# CurrentSensors.net
KiCad netlist of a schematic drawn in Altium Designer
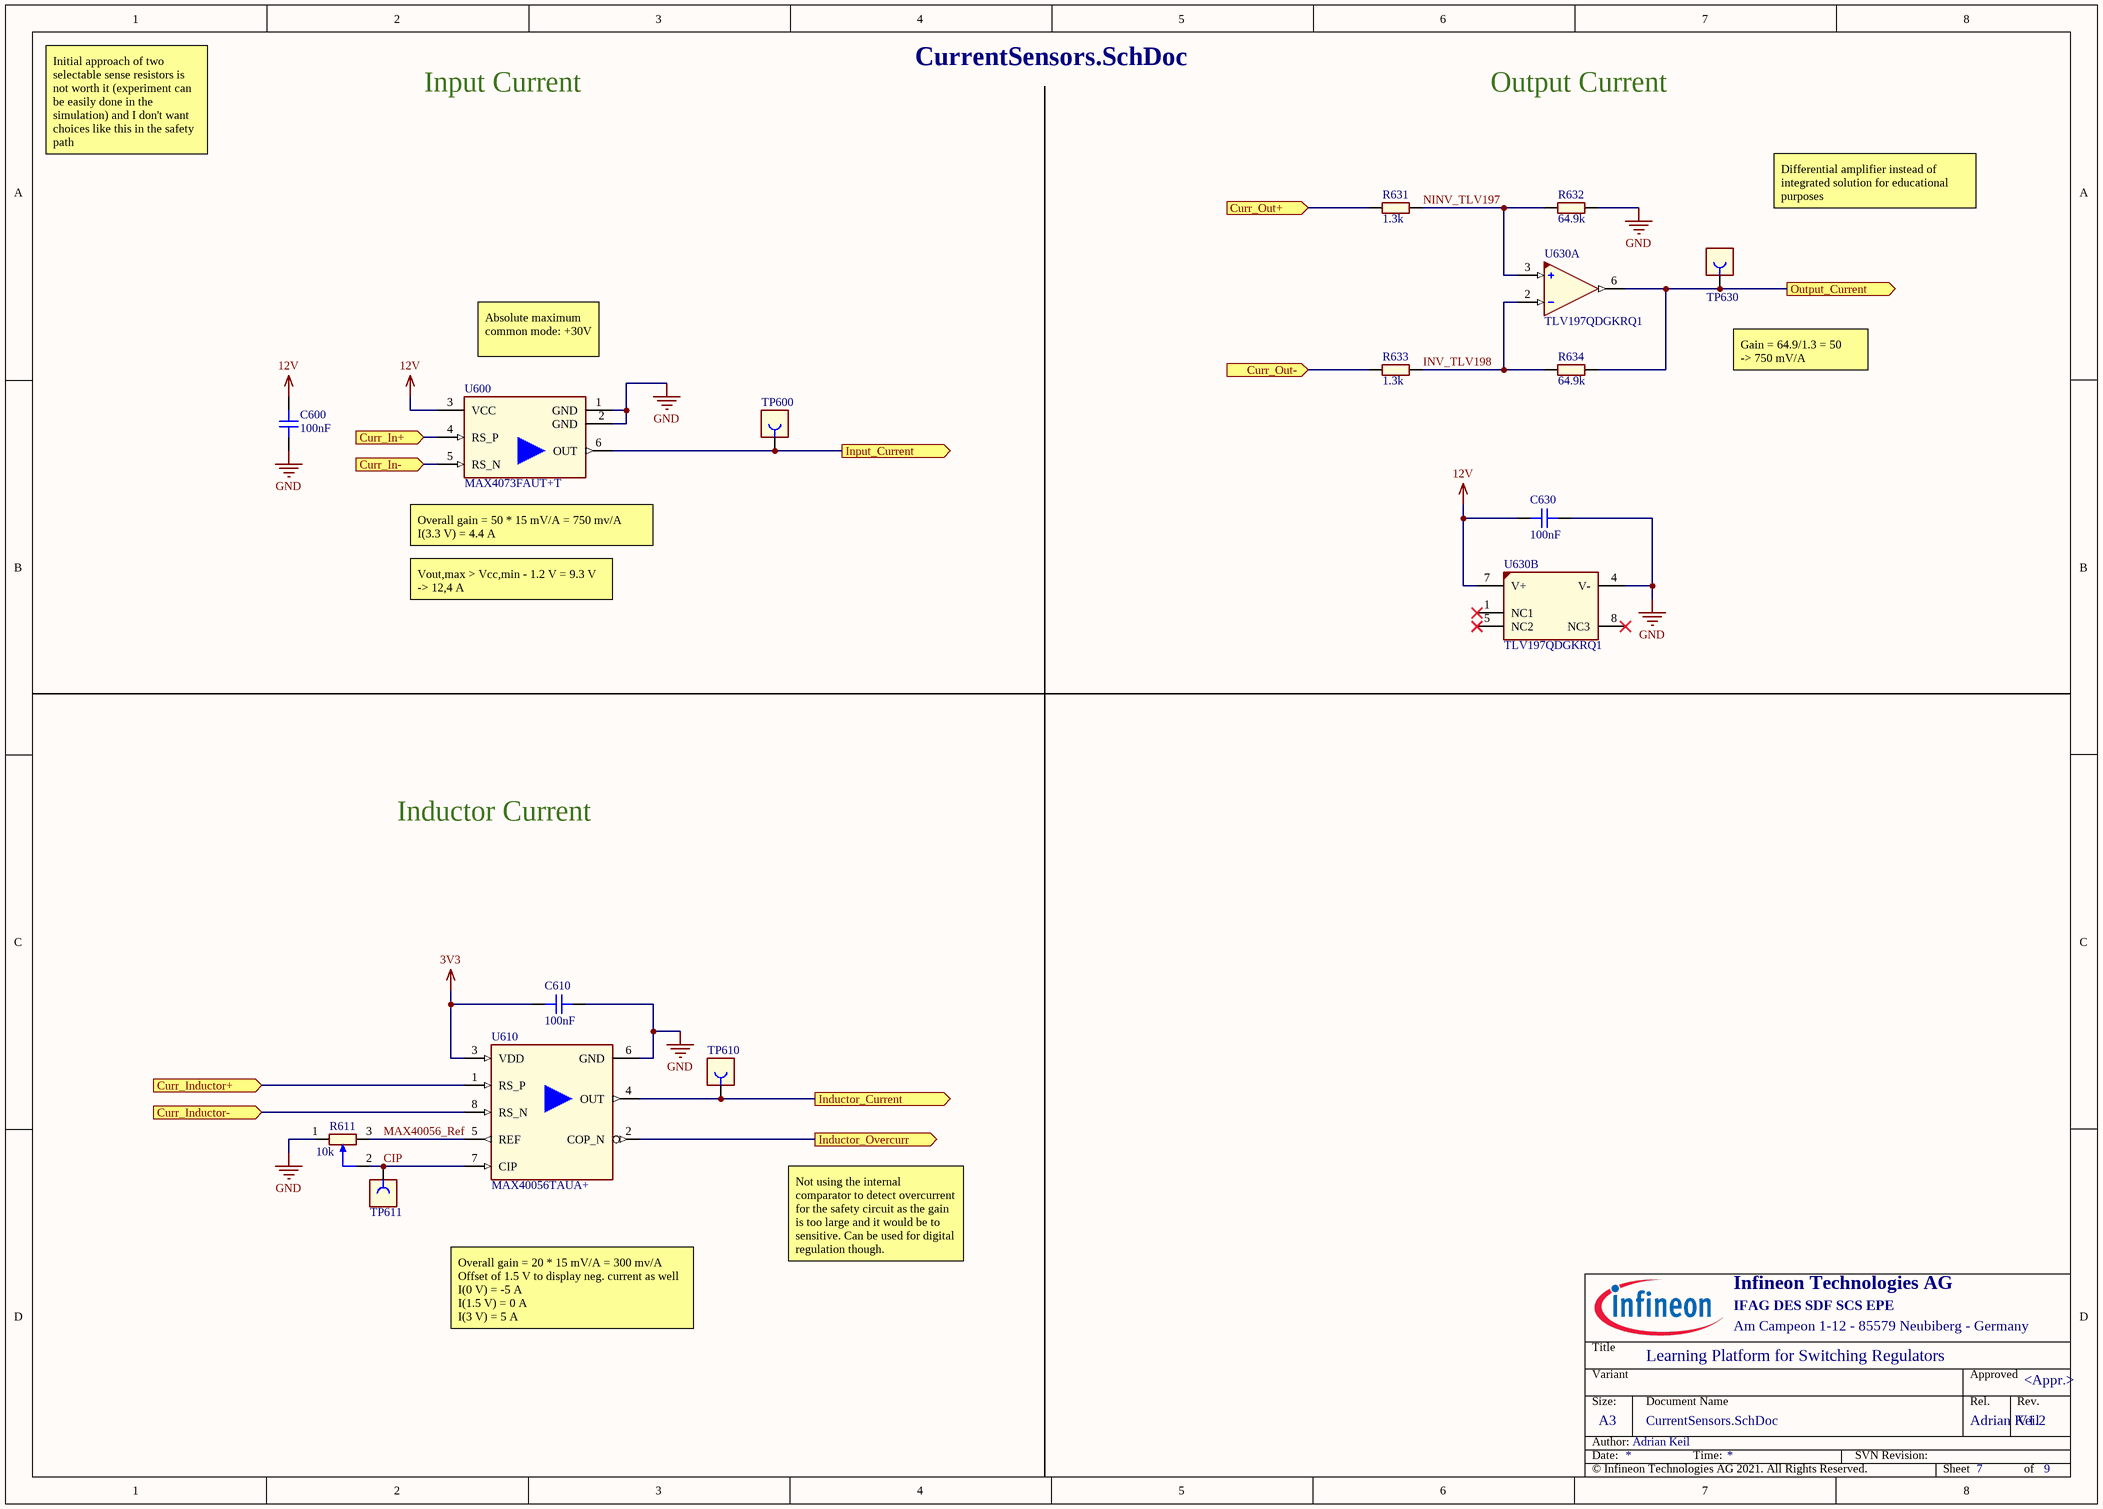
[diagram p0: CurrentSensors.SchDoc]

(export (version "E")
  (design (tool "Eeschema 10.0.6"))
  (components
    (comp (ref "C600")
      (value "100nF")
      (footprint "CAPC1608X90N-2")
      (description "CAP / CERA / 100nF / 50V / 10% / X7R (EIA) / -55°C to 125°C / 0603 / SMD / -")
      (fields (field (name "MANUFACTURER") "AVX"))
      (libsource (lib "PCBLibraryData") (part "CAP-SGL-STD-02P_00000001"))
    )
    (comp (ref "C610")
      (value "100nF")
      (footprint "CAPC1608X90N-2")
      (description "CAP / CERA / 100nF / 50V / 10% / X7R (EIA) / -55°C to 125°C / 0603 / SMD / -")
      (fields (field (name "MANUFACTURER") "AVX"))
      (libsource (lib "PCBLibraryData") (part "CAP-SGL-STD-02P_00000001"))
    )
    (comp (ref "C630")
      (value "100nF")
      (footprint "CAPC1608X90N-2")
      (description "CAP / CERA / 100nF / 50V / 10% / X7R (EIA) / -55°C to 125°C / 0603 / SMD / -")
      (fields (field (name "MANUFACTURER") "AVX"))
      (libsource (lib "PCBLibraryData") (part "CAP-SGL-STD-02P_00000001"))
    )
    (comp (ref "R611")
      (value "10k")
      (footprint "POT-SMD-3361P")
      (fields (field (name "MANUFACTURER") "Bourns"))
      (libsource (lib "PCBLibraryData") (part "RES-SGL-VAR-03P_00000026"))
    )
    (comp (ref "R631")
      (value "1.3k")
      (footprint "RESC1609X50N")
      (description "RES / STD / 1.3k / 100mW / 1% / 100ppm/K / -55°C to 155°C / 0603 / SMD / -")
      (fields (field (name "LEGACY PARTNUMBER") "RES01801155") (field (name "MANUFACTURER") "Vishay"))
      (libsource (lib "") (part "RES-SGL-STD-02P_00000006_1"))
    )
    (comp (ref "R632")
      (value "64.9k")
      (footprint "RESC1609X50N")
      (description "RES / STD / 64.9k / 100mW / 1% / 100ppm/K / -55°C to 155°C / 0603 / SMD / -")
      (fields (field (name "LEGACY PARTNUMBER") "RES01801350") (field (name "MANUFACTURER") "Vishay"))
      (libsource (lib "PCBLibraryData") (part "RES-SGL-STD-02P_00000006"))
    )
    (comp (ref "R633")
      (value "1.3k")
      (footprint "RESC1609X50N")
      (description "RES / STD / 1.3k / 100mW / 1% / 100ppm/K / -55°C to 155°C / 0603 / SMD / -")
      (fields (field (name "LEGACY PARTNUMBER") "RES01801155") (field (name "MANUFACTURER") "Vishay"))
      (libsource (lib "") (part "RES-SGL-STD-02P_00000006_1"))
    )
    (comp (ref "R634")
      (value "64.9k")
      (footprint "RESC1609X50N")
      (description "RES / STD / 64.9k / 100mW / 1% / 100ppm/K / -55°C to 155°C / 0603 / SMD / -")
      (fields (field (name "LEGACY PARTNUMBER") "RES01801350") (field (name "MANUFACTURER") "Vishay"))
      (libsource (lib "") (part "RES-SGL-STD-02P_00000006_1"))
    )
    (comp (ref "TP600")
      (value "S1751-46R")
      (footprint "CON-SMD-TT-S1751-46")
      (description "Test Terminal, Surface Mount (Tape and Reeled Components)")
      (fields (field (name "LEGACY PARTNUMBER") "CON01501015") (field (name "MANUFACTURER") "Harwin"))
      (libsource (lib "PCBLibraryData") (part "connector_1_f"))
    )
    (comp (ref "TP610")
      (value "S1751-46R")
      (footprint "CON-SMD-TT-S1751-46")
      (description "Test Terminal, Surface Mount (Tape and Reeled Components)")
      (fields (field (name "LEGACY PARTNUMBER") "CON01501015") (field (name "MANUFACTURER") "Harwin"))
      (libsource (lib "PCBLibraryData") (part "connector_1_f"))
    )
    (comp (ref "TP611")
      (value "S1751-46R")
      (footprint "CON-SMD-TT-S1751-46")
      (description "Test Terminal, Surface Mount (Tape and Reeled Components)")
      (fields (field (name "LEGACY PARTNUMBER") "CON01501015") (field (name "MANUFACTURER") "Harwin"))
      (libsource (lib "") (part "connector_1_f_1"))
    )
    (comp (ref "TP630")
      (value "S1751-46R")
      (footprint "CON-SMD-TT-S1751-46")
      (description "Test Terminal, Surface Mount (Tape and Reeled Components)")
      (fields (field (name "LEGACY PARTNUMBER") "CON01501015") (field (name "MANUFACTURER") "Harwin"))
      (libsource (lib "PCBLibraryData") (part "connector_1_f"))
    )
    (comp (ref "U600")
      (value "MAX4073FAUT+T")
      (footprint "SOT95P280X145-6N-2-V")
      (description "Low-Cost, Voltage-Output, High-Side Current-Sense Amplifier")
      (fields (field (name "MANUFACTURER") "Maxim Integrated Products"))
      (libsource (lib "PCBLibraryData") (part "MAX4073xAUT"))
    )
    (comp (ref "U610")
      (value "MAX40056TAUA+")
      (footprint "SOP65P490X110-8N-4")
      (description "Current Sense Amplifiers Current-Sense Amplifier W / PWM Rejection")
      (fields (field (name "MANUFACTURER") "Maxim Integrated Products"))
      (libsource (lib "PCBLibraryData") (part "MAX40056xAUA"))
    )
    (comp (ref "U630")
      (value "TLV197QDGKRQ1")
      (footprint "SOP65P490X110-8N-V")
      (fields (field (name "MANUFACTURER") "Texas Instruments"))
      (libsource (lib "PCBLibraryData") (part "OPA140AID"))
    )
  )
  (nets
    (net (code "1") (name "/CIP") (class "Default")
      (node (ref "R611") (pin "2") (pinfunction "2_2") (pintype "passive"))
      (node (ref "TP611") (pin "1") (pinfunction "1_1") (pintype "passive"))
      (node (ref "U610") (pin "7") (pinfunction "CIP_7") (pintype "input"))
    )
    (net (code "2") (name "/Curr_In+") (class "Default")
      (node (ref "U600") (pin "4") (pinfunction "RS_P_4") (pintype "input"))
    )
    (net (code "3") (name "/Curr_In-") (class "Default")
      (node (ref "U600") (pin "5") (pinfunction "RS_N_5") (pintype "input"))
    )
    (net (code "4") (name "/Curr_Inductor+") (class "Default")
      (node (ref "U610") (pin "1") (pinfunction "RS_P_1") (pintype "input"))
    )
    (net (code "5") (name "/Curr_Inductor-") (class "Default")
      (node (ref "U610") (pin "8") (pinfunction "RS_N_8") (pintype "input"))
    )
    (net (code "6") (name "/Curr_Out+") (class "Default")
      (node (ref "R631") (pin "1") (pinfunction "1_1") (pintype "passive"))
    )
    (net (code "7") (name "/Curr_Out-") (class "Default")
      (node (ref "R633") (pin "1") (pinfunction "1_1") (pintype "passive"))
    )
    (net (code "8") (name "/INV_TLV198") (class "Default")
      (node (ref "R633") (pin "2") (pinfunction "2_2") (pintype "passive"))
      (node (ref "R634") (pin "1") (pinfunction "1_1") (pintype "passive"))
      (node (ref "U630") (pin "2") (pinfunction "IN_N_2") (pintype "input"))
    )
    (net (code "9") (name "/Inductor_Current") (class "Default")
      (node (ref "TP610") (pin "1") (pinfunction "1_1") (pintype "passive"))
      (node (ref "U610") (pin "4") (pinfunction "OUT_4") (pintype "output"))
    )
    (net (code "10") (name "/Inductor_Overcurr") (class "Default")
      (node (ref "U610") (pin "2") (pinfunction "COP_N_2") (pintype "output"))
    )
    (net (code "11") (name "/Input_Current") (class "Default")
      (node (ref "TP600") (pin "1") (pinfunction "1_1") (pintype "passive"))
      (node (ref "U600") (pin "6") (pinfunction "OUT_6") (pintype "output"))
    )
    (net (code "12") (name "/MAX40056_Ref") (class "Default")
      (node (ref "R611") (pin "3") (pinfunction "3_3") (pintype "passive"))
      (node (ref "U610") (pin "5") (pinfunction "REF_5") (pintype "output"))
    )
    (net (code "13") (name "/NINV_TLV197") (class "Default")
      (node (ref "R631") (pin "2") (pinfunction "2_2") (pintype "passive"))
      (node (ref "R632") (pin "2") (pinfunction "2_2") (pintype "passive"))
      (node (ref "U630") (pin "3") (pinfunction "IN_P_3") (pintype "input"))
    )
    (net (code "14") (name "/Output_Current") (class "Default")
      (node (ref "R634") (pin "2") (pinfunction "2_2") (pintype "passive"))
      (node (ref "TP630") (pin "1") (pinfunction "1_1") (pintype "passive"))
      (node (ref "U630") (pin "6") (pinfunction "OUT_6") (pintype "output"))
    )
    (net (code "15") (name "3V3") (class "Default")
      (node (ref "C610") (pin "2") (pinfunction "2_2") (pintype "passive"))
      (node (ref "U610") (pin "3") (pinfunction "VDD_3") (pintype "input"))
    )
    (net (code "16") (name "12V") (class "Default")
      (node (ref "C600") (pin "2") (pinfunction "2_2") (pintype "passive"))
      (node (ref "C630") (pin "2") (pinfunction "2_2") (pintype "passive"))
      (node (ref "U600") (pin "3") (pinfunction "VCC_3") (pintype "power_in"))
      (node (ref "U630") (pin "7") (pinfunction "V+_7") (pintype "power_in"))
    )
    (net (code "17") (name "GND") (class "Default")
      (node (ref "C600") (pin "1") (pinfunction "1_1") (pintype "passive"))
      (node (ref "C610") (pin "1") (pinfunction "1_1") (pintype "passive"))
      (node (ref "C630") (pin "1") (pinfunction "1_1") (pintype "passive"))
      (node (ref "R611") (pin "1") (pinfunction "1_1") (pintype "passive"))
      (node (ref "R632") (pin "1") (pinfunction "1_1") (pintype "passive"))
      (node (ref "U600") (pin "1") (pinfunction "GND_1") (pintype "power_in"))
      (node (ref "U600") (pin "2") (pinfunction "GND_2") (pintype "power_in"))
      (node (ref "U610") (pin "6") (pinfunction "GND_6") (pintype "power_in"))
      (node (ref "U630") (pin "4") (pinfunction "V-_4") (pintype "power_in"))
    )
    (net (code "18") (name "unconnected-(U630B-NC1-Pad1)") (class "Default")
      (node (ref "U630") (pin "1") (pinfunction "NC1_1") (pintype "passive+no_connect"))
    )
    (net (code "19") (name "unconnected-(U630B-NC2-Pad5)") (class "Default")
      (node (ref "U630") (pin "5") (pinfunction "NC2_5") (pintype "passive+no_connect"))
    )
    (net (code "20") (name "unconnected-(U630B-NC3-Pad8)") (class "Default")
      (node (ref "U630") (pin "8") (pinfunction "NC3_8") (pintype "passive+no_connect"))
    )
  )
)
